# board1.net
KiCad netlist of a schematic drawn in EAGLE
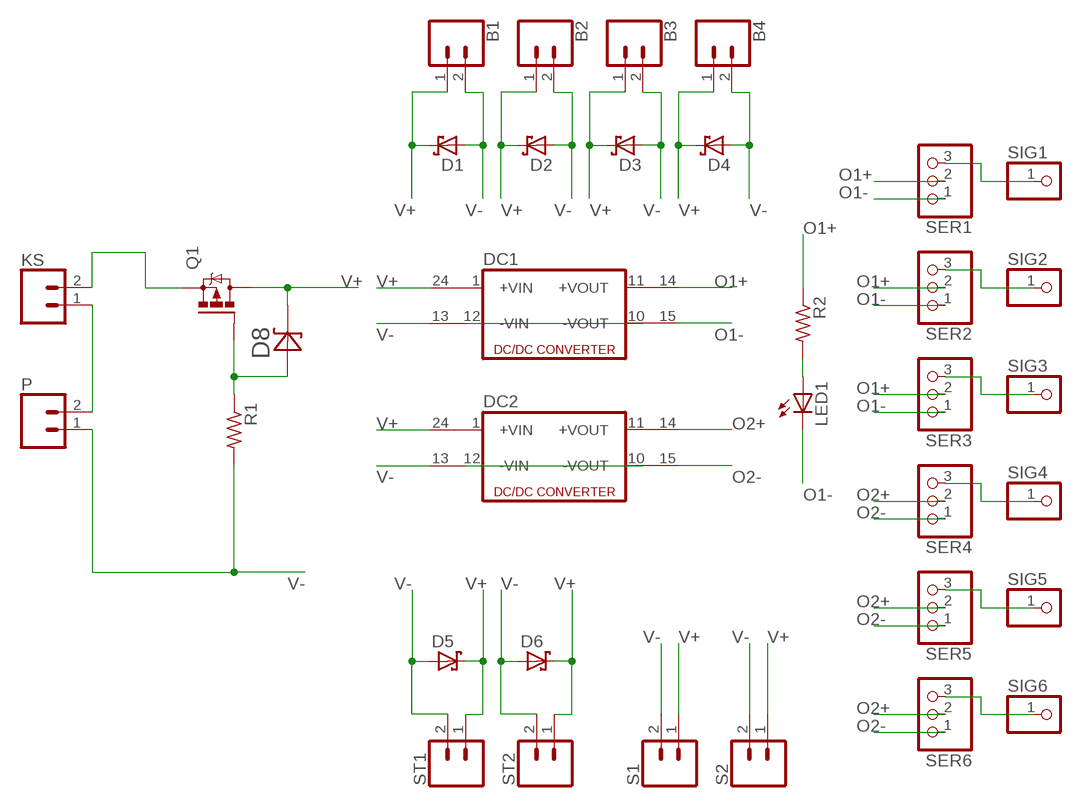
[diagram p0: schematic, sheet 1]

(export (version "E")
  (design (tool "Eeschema 10.0.6"))
  (components
    (comp (ref "B1")
      (value "CONN_02")
      (footprint "eagle-import:1X02")
      (libsource (lib "eagle-import") (part "CONN_02"))
    )
    (comp (ref "B2")
      (value "CONN_02")
      (footprint "eagle-import:1X02")
      (libsource (lib "eagle-import") (part "CONN_02"))
    )
    (comp (ref "B3")
      (value "CONN_02")
      (footprint "eagle-import:1X02")
      (libsource (lib "eagle-import") (part "CONN_02"))
    )
    (comp (ref "B4")
      (value "CONN_02")
      (footprint "eagle-import:1X02")
      (libsource (lib "eagle-import") (part "CONN_02"))
    )
    (comp (ref "D1")
      (value "SCHOTTKY-DIODEAG")
      (footprint "eagle-import:AG")
      (libsource (lib "eagle-import") (part "SCHOTTKY-DIODEAG"))
    )
    (comp (ref "D2")
      (value "SCHOTTKY-DIODEAG")
      (footprint "eagle-import:AG")
      (libsource (lib "eagle-import") (part "SCHOTTKY-DIODEAG"))
    )
    (comp (ref "D3")
      (value "SCHOTTKY-DIODEAG")
      (footprint "eagle-import:AG")
      (libsource (lib "eagle-import") (part "SCHOTTKY-DIODEAG"))
    )
    (comp (ref "D4")
      (value "SCHOTTKY-DIODEAG")
      (footprint "eagle-import:AG")
      (libsource (lib "eagle-import") (part "SCHOTTKY-DIODEAG"))
    )
    (comp (ref "D5")
      (value "SCHOTTKY-DIODEAG")
      (footprint "eagle-import:AG")
      (libsource (lib "eagle-import") (part "SCHOTTKY-DIODEAG"))
    )
    (comp (ref "D6")
      (value "SCHOTTKY-DIODEAG")
      (footprint "eagle-import:AG")
      (libsource (lib "eagle-import") (part "SCHOTTKY-DIODEAG"))
    )
    (comp (ref "D8")
      (value "1N4752A-T")
      (footprint "eagle-import:DIOAD1060W80L410D260")
      (fields (field (name "MF") "ON Semiconductor") (field (name "MP") "1N4752A"))
      (libsource (lib "eagle-import") (part "1N4752A-T"))
    )
    (comp (ref "DC1")
      (value "DC213R")
      (footprint "eagle-import:CMK")
      (libsource (lib "eagle-import") (part "DC213R"))
    )
    (comp (ref "DC2")
      (value "DC213R")
      (footprint "eagle-import:CMK")
      (libsource (lib "eagle-import") (part "DC213R"))
    )
    (comp (ref "KS")
      (value "CONN_02")
      (footprint "eagle-import:1X02")
      (libsource (lib "eagle-import") (part "CONN_02"))
    )
    (comp (ref "LED1")
      (value "LED5MM")
      (footprint "eagle-import:LED5MM")
      (libsource (lib "eagle-import") (part "LED5MM"))
    )
    (comp (ref "P")
      (value "CONN_02")
      (footprint "eagle-import:1X02")
      (libsource (lib "eagle-import") (part "CONN_02"))
    )
    (comp (ref "Q1")
      (value "IRF9530")
      (footprint "eagle-import:TO220BV")
      (libsource (lib "eagle-import") (part "IRF9530"))
    )
    (comp (ref "R1")
      (value "R-US_0207/10")
      (footprint "eagle-import:0207_10")
      (libsource (lib "eagle-import") (part "R-US_0207/10"))
    )
    (comp (ref "R2")
      (value "R-US_0207/10")
      (footprint "eagle-import:0207_10")
      (libsource (lib "eagle-import") (part "R-US_0207/10"))
    )
    (comp (ref "S1")
      (value "CONN_02")
      (footprint "eagle-import:1X02")
      (libsource (lib "eagle-import") (part "CONN_02"))
    )
    (comp (ref "S2")
      (value "CONN_02")
      (footprint "eagle-import:1X02")
      (libsource (lib "eagle-import") (part "CONN_02"))
    )
    (comp (ref "SER1")
      (value "PINHD-1X3")
      (footprint "eagle-import:1X03")
      (libsource (lib "eagle-import") (part "PINHD-1X3"))
    )
    (comp (ref "SER2")
      (value "PINHD-1X3")
      (footprint "eagle-import:1X03")
      (libsource (lib "eagle-import") (part "PINHD-1X3"))
    )
    (comp (ref "SER3")
      (value "PINHD-1X3")
      (footprint "eagle-import:1X03")
      (libsource (lib "eagle-import") (part "PINHD-1X3"))
    )
    (comp (ref "SER4")
      (value "PINHD-1X3")
      (footprint "eagle-import:1X03")
      (libsource (lib "eagle-import") (part "PINHD-1X3"))
    )
    (comp (ref "SER5")
      (value "PINHD-1X3")
      (footprint "eagle-import:1X03")
      (libsource (lib "eagle-import") (part "PINHD-1X3"))
    )
    (comp (ref "SER6")
      (value "PINHD-1X3")
      (footprint "eagle-import:1X03")
      (libsource (lib "eagle-import") (part "PINHD-1X3"))
    )
    (comp (ref "SIG1")
      (value "PINHD-1X1")
      (footprint "eagle-import:1X01")
      (libsource (lib "eagle-import") (part "PINHD-1X1"))
    )
    (comp (ref "SIG2")
      (value "PINHD-1X1")
      (footprint "eagle-import:1X01")
      (libsource (lib "eagle-import") (part "PINHD-1X1"))
    )
    (comp (ref "SIG3")
      (value "PINHD-1X1")
      (footprint "eagle-import:1X01")
      (libsource (lib "eagle-import") (part "PINHD-1X1"))
    )
    (comp (ref "SIG4")
      (value "PINHD-1X1")
      (footprint "eagle-import:1X01")
      (libsource (lib "eagle-import") (part "PINHD-1X1"))
    )
    (comp (ref "SIG5")
      (value "PINHD-1X1")
      (footprint "eagle-import:1X01")
      (libsource (lib "eagle-import") (part "PINHD-1X1"))
    )
    (comp (ref "SIG6")
      (value "PINHD-1X1")
      (footprint "eagle-import:1X01")
      (libsource (lib "eagle-import") (part "PINHD-1X1"))
    )
    (comp (ref "ST1")
      (value "CONN_02")
      (footprint "eagle-import:1X02")
      (libsource (lib "eagle-import") (part "CONN_02"))
    )
    (comp (ref "ST2")
      (value "CONN_02")
      (footprint "eagle-import:1X02")
      (libsource (lib "eagle-import") (part "CONN_02"))
    )
  )
  (nets
    (net (code "1") (name "/O1+") (class "Default")
      (node (ref "DC1") (pin "14") (pinfunction "+VOUT1_14") (pintype "passive"))
      (node (ref "R2") (pin "1") (pinfunction "1_1") (pintype "passive"))
      (node (ref "SER1") (pin "2") (pinfunction "2_2") (pintype "passive"))
      (node (ref "SER2") (pin "2") (pinfunction "2_2") (pintype "passive"))
      (node (ref "SER3") (pin "2") (pinfunction "2_2") (pintype "passive"))
    )
    (net (code "2") (name "/O1-") (class "Default")
      (node (ref "DC1") (pin "15") (pinfunction "-VOUT1_15") (pintype "passive"))
      (node (ref "LED1") (pin "K") (pinfunction "C_K") (pintype "passive"))
      (node (ref "SER1") (pin "1") (pinfunction "1_1") (pintype "passive"))
      (node (ref "SER2") (pin "1") (pinfunction "1_1") (pintype "passive"))
      (node (ref "SER3") (pin "1") (pinfunction "1_1") (pintype "passive"))
    )
    (net (code "3") (name "/O2+") (class "Default")
      (node (ref "DC2") (pin "14") (pinfunction "+VOUT1_14") (pintype "passive"))
      (node (ref "SER4") (pin "2") (pinfunction "2_2") (pintype "passive"))
      (node (ref "SER5") (pin "2") (pinfunction "2_2") (pintype "passive"))
      (node (ref "SER6") (pin "2") (pinfunction "2_2") (pintype "passive"))
    )
    (net (code "4") (name "/O2-") (class "Default")
      (node (ref "DC2") (pin "15") (pinfunction "-VOUT1_15") (pintype "passive"))
      (node (ref "SER4") (pin "1") (pinfunction "1_1") (pintype "passive"))
      (node (ref "SER5") (pin "1") (pinfunction "1_1") (pintype "passive"))
      (node (ref "SER6") (pin "1") (pinfunction "1_1") (pintype "passive"))
    )
    (net (code "5") (name "/V+") (class "Default")
      (node (ref "B1") (pin "1") (pinfunction "1_1") (pintype "passive"))
      (node (ref "B2") (pin "1") (pinfunction "1_1") (pintype "passive"))
      (node (ref "B3") (pin "1") (pinfunction "1_1") (pintype "passive"))
      (node (ref "B4") (pin "1") (pinfunction "1_1") (pintype "passive"))
      (node (ref "D1") (pin "C") (pinfunction "C_C") (pintype "passive"))
      (node (ref "D2") (pin "C") (pinfunction "C_C") (pintype "passive"))
      (node (ref "D3") (pin "C") (pinfunction "C_C") (pintype "passive"))
      (node (ref "D4") (pin "C") (pinfunction "C_C") (pintype "passive"))
      (node (ref "D5") (pin "C") (pinfunction "C_C") (pintype "passive"))
      (node (ref "D6") (pin "C") (pinfunction "C_C") (pintype "passive"))
      (node (ref "D8") (pin "C") (pinfunction "C_C") (pintype "passive"))
      (node (ref "DC1") (pin "24") (pinfunction "+VIN1_24") (pintype "passive"))
      (node (ref "DC2") (pin "24") (pinfunction "+VIN1_24") (pintype "passive"))
      (node (ref "Q1") (pin "D") (pinfunction "D_D") (pintype "passive"))
      (node (ref "S1") (pin "1") (pinfunction "1_1") (pintype "passive"))
      (node (ref "S2") (pin "1") (pinfunction "1_1") (pintype "passive"))
      (node (ref "ST1") (pin "1") (pinfunction "1_1") (pintype "passive"))
      (node (ref "ST2") (pin "1") (pinfunction "1_1") (pintype "passive"))
    )
    (net (code "6") (name "/V-") (class "Default")
      (node (ref "B1") (pin "2") (pinfunction "2_2") (pintype "passive"))
      (node (ref "B2") (pin "2") (pinfunction "2_2") (pintype "passive"))
      (node (ref "B3") (pin "2") (pinfunction "2_2") (pintype "passive"))
      (node (ref "B4") (pin "2") (pinfunction "2_2") (pintype "passive"))
      (node (ref "D1") (pin "A") (pinfunction "A_A") (pintype "passive"))
      (node (ref "D2") (pin "A") (pinfunction "A_A") (pintype "passive"))
      (node (ref "D3") (pin "A") (pinfunction "A_A") (pintype "passive"))
      (node (ref "D4") (pin "A") (pinfunction "A_A") (pintype "passive"))
      (node (ref "D5") (pin "A") (pinfunction "A_A") (pintype "passive"))
      (node (ref "D6") (pin "A") (pinfunction "A_A") (pintype "passive"))
      (node (ref "DC1") (pin "13") (pinfunction "-VIN1_13") (pintype "passive"))
      (node (ref "DC2") (pin "13") (pinfunction "-VIN1_13") (pintype "passive"))
      (node (ref "P") (pin "1") (pinfunction "1_1") (pintype "passive"))
      (node (ref "R1") (pin "2") (pinfunction "2_2") (pintype "passive"))
      (node (ref "S1") (pin "2") (pinfunction "2_2") (pintype "passive"))
      (node (ref "S2") (pin "2") (pinfunction "2_2") (pintype "passive"))
      (node (ref "ST1") (pin "2") (pinfunction "2_2") (pintype "passive"))
      (node (ref "ST2") (pin "2") (pinfunction "2_2") (pintype "passive"))
    )
    (net (code "7") (name "Net-(D8-PadA)") (class "Default")
      (node (ref "D8") (pin "A") (pinfunction "A_A") (pintype "passive"))
      (node (ref "Q1") (pin "G") (pinfunction "G_G") (pintype "passive"))
      (node (ref "R1") (pin "1") (pinfunction "1_1") (pintype "passive"))
    )
    (net (code "8") (name "Net-(DC1--VIN)") (class "Default")
      (node (ref "DC1") (pin "10") (pinfunction "-VOUT_10") (pintype "passive"))
      (node (ref "DC1") (pin "12") (pinfunction "-VIN_12") (pintype "passive"))
    )
    (net (code "9") (name "Net-(DC2--VIN)") (class "Default")
      (node (ref "DC2") (pin "10") (pinfunction "-VOUT_10") (pintype "passive"))
      (node (ref "DC2") (pin "12") (pinfunction "-VIN_12") (pintype "passive"))
    )
    (net (code "10") (name "Net-(KS-Pad1)") (class "Default")
      (node (ref "KS") (pin "1") (pinfunction "1_1") (pintype "passive"))
      (node (ref "P") (pin "2") (pinfunction "2_2") (pintype "passive"))
    )
    (net (code "11") (name "Net-(KS-Pad2)") (class "Default")
      (node (ref "KS") (pin "2") (pinfunction "2_2") (pintype "passive"))
      (node (ref "Q1") (pin "S") (pinfunction "S_S") (pintype "passive"))
    )
    (net (code "12") (name "Net-(LED1-PadA)") (class "Default")
      (node (ref "LED1") (pin "A") (pinfunction "A_A") (pintype "passive"))
      (node (ref "R2") (pin "2") (pinfunction "2_2") (pintype "passive"))
    )
    (net (code "13") (name "Net-(SER1-Pad3)") (class "Default")
      (node (ref "SER1") (pin "3") (pinfunction "3_3") (pintype "passive"))
      (node (ref "SIG1") (pin "1") (pinfunction "1_1") (pintype "passive"))
    )
    (net (code "14") (name "Net-(SER2-Pad3)") (class "Default")
      (node (ref "SER2") (pin "3") (pinfunction "3_3") (pintype "passive"))
      (node (ref "SIG2") (pin "1") (pinfunction "1_1") (pintype "passive"))
    )
    (net (code "15") (name "Net-(SER3-Pad3)") (class "Default")
      (node (ref "SER3") (pin "3") (pinfunction "3_3") (pintype "passive"))
      (node (ref "SIG3") (pin "1") (pinfunction "1_1") (pintype "passive"))
    )
    (net (code "16") (name "Net-(SER4-Pad3)") (class "Default")
      (node (ref "SER4") (pin "3") (pinfunction "3_3") (pintype "passive"))
      (node (ref "SIG4") (pin "1") (pinfunction "1_1") (pintype "passive"))
    )
    (net (code "17") (name "Net-(SER5-Pad3)") (class "Default")
      (node (ref "SER5") (pin "3") (pinfunction "3_3") (pintype "passive"))
      (node (ref "SIG5") (pin "1") (pinfunction "1_1") (pintype "passive"))
    )
    (net (code "18") (name "Net-(SER6-Pad3)") (class "Default")
      (node (ref "SER6") (pin "3") (pinfunction "3_3") (pintype "passive"))
      (node (ref "SIG6") (pin "1") (pinfunction "1_1") (pintype "passive"))
    )
    (net (code "19") (name "unconnected-(DC1-+VIN-Pad1)") (class "Default")
      (node (ref "DC1") (pin "1") (pinfunction "+VIN_1") (pintype "passive"))
    )
    (net (code "20") (name "unconnected-(DC1-+VOUT-Pad11)") (class "Default")
      (node (ref "DC1") (pin "11") (pinfunction "+VOUT_11") (pintype "passive"))
    )
    (net (code "21") (name "unconnected-(DC2-+VIN-Pad1)") (class "Default")
      (node (ref "DC2") (pin "1") (pinfunction "+VIN_1") (pintype "passive"))
    )
    (net (code "22") (name "unconnected-(DC2-+VOUT-Pad11)") (class "Default")
      (node (ref "DC2") (pin "11") (pinfunction "+VOUT_11") (pintype "passive"))
    )
  )
)
